# power.net
KiCad netlist of a schematic drawn in Altium Designer
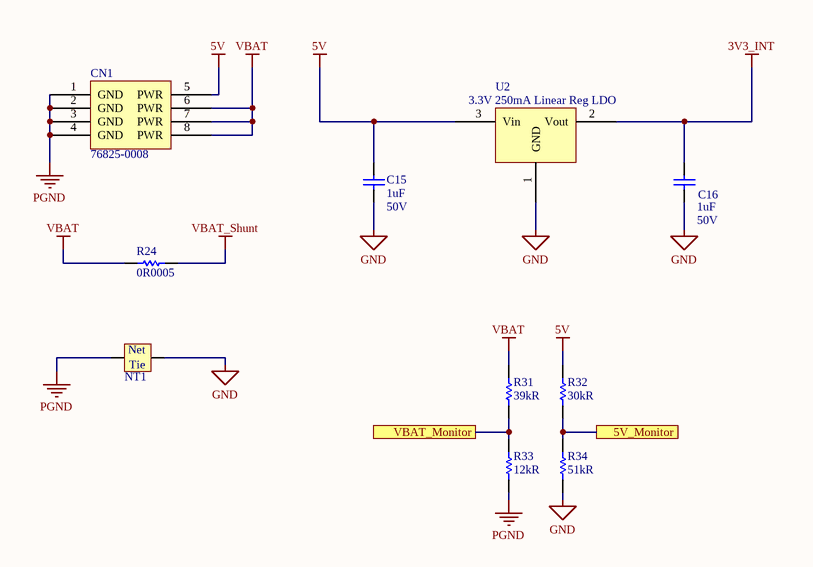
[diagram p0: power.SchDoc]

(export (version "E")
  (design (tool "Eeschema 10.0.6"))
  (components
    (comp (ref "C15")
      (value "CL21B105KBFNNNG")
      (footprint "0803 CAP")
      (description "SAMSUNG ELECTRO-MECHANICS - CL21B105KBFNNNG - MLCC CAPACITORS")
      (fields
        (field (name "CAPACITANCE") "1uF")
        (field (name "TOLERANCE") "10%")
        (field (name "VOLTAGE") "50V")
      )
      (libsource (lib "AUVIC") (part "Symbol"))
    )
    (comp (ref "C16")
      (value "CL21B105KBFNNNG")
      (footprint "0803 CAP")
      (description "SAMSUNG ELECTRO-MECHANICS - CL21B105KBFNNNG - MLCC CAPACITORS")
      (fields
        (field (name "TOLERANCE") "10%")
        (field (name "CAPACITANCE") "1uF")
        (field (name "VOLTAGE") "50V")
      )
      (libsource (lib "AUVIC") (part "Symbol"))
    )
    (comp (ref "CN1")
      (value "76825-0008")
      (footprint "76825-0008-Footprint-1")
      (description "MOLEX         76825-0008.             CONNECTOR, HEADER, 8POS, 2ROW, 5.7MM")
      (libsource (lib "AUVIC") (part "76825-0008"))
    )
    (comp (ref "NT1")
      (value "Net Tie, 20x3mm")
      (footprint "NETTIE_20x3mm")
      (fields
        (field (name "SOURCE") "AUVic_Integrated_Library_Virtual_Components.SchLib")
        (field (name "CREATED BY") "Ashwin Sira")
        (field (name "PUBLISHER") "AUVic")
      )
      (libsource (lib "") (part "Symbol_1"))
    )
    (comp (ref "R24")
      (value "0R0005")
      (footprint "RESC6332N(2512\")")
      (description "0R0005, 1%, 3W, 2512 SMD")
      (fields
        (field (name "MFG") "Riedon")
        (field (name "CREATED BY") "Ashwin Sira")
        (field (name "PUBLISHER") "AUVic")
      )
      (libsource (lib "") (part "Symbol_2"))
    )
    (comp (ref "R31")
      (value "CRCW060339K0FKEA")
      (footprint "FP-CRCW0603-e3-IPC_C")
      (description "Resistor; Thick Film; 39 Kilohms; 0.1 W; 1%; SMT; 0603; TCR 37 ppm/DegC; Cut Tape")
      (fields (field (name "RESISTANCE") "39kR") (field (name "TOLERANCE") "1%"))
      (libsource (lib "AUVIC") (part "RES"))
    )
    (comp (ref "R32")
      (value "CRCW060330K0FKEA")
      (footprint "RESC1609X50X30NL10T20")
      (description "Resistor SMD 30 kOhm 0603 PU=5000 ST, CRCW060330K0FKEA, Vishay")
      (fields (field (name "RESISTANCE") "30kR") (field (name "TOLERANCE") "1%"))
      (libsource (lib "AUVIC") (part "RES"))
    )
    (comp (ref "R33")
      (value "12kR, 1%, 1/10W, 0603")
      (footprint "RESC0603(1608)_L")
      (description "TE Connectivity CRG0603 Series Thick Film Surface Mount Resistor 0603 Case 12k 1% 0.1W 100ppm/C")
      (fields (field (name "TOLERANCE") "1%") (field (name "RESISTANCE") "12kR"))
      (libsource (lib "AUVIC") (part "RES"))
    )
    (comp (ref "R34")
      (value "CRCW060351K0FKEA")
      (footprint "RESC0603(1608)_N")
      (fields (field (name "RESISTANCE") "51kR") (field (name "TOLERANCE") "1%"))
      (libsource (lib "AUVIC") (part "RES"))
    )
    (comp (ref "U2")
      (value "3.3V 250mA Linear Reg LDO")
      (footprint "SOT95P245X110-3N")
      (description "IC REG LINEAR 3.3V 250MA SOT23-3")
      (fields (field (name "CREATED BY") "Poorna Chander Kalidas"))
      (libsource (lib "AUVIC") (part "3.3V 250mA Linear Reg LDO"))
    )
  )
  (nets
    (net (code "1") (name "/5V_Monitor") (class "Default")
      (node (ref "R32") (pin "2") (pinfunction "2_2") (pintype "passive"))
      (node (ref "R34") (pin "2") (pinfunction "2_2") (pintype "passive"))
    )
    (net (code "2") (name "/VBAT_Monitor") (class "Default")
      (node (ref "R31") (pin "1") (pinfunction "1_1") (pintype "passive"))
      (node (ref "R33") (pin "2") (pinfunction "2_2") (pintype "passive"))
    )
    (net (code "3") (name "3V3_INT") (class "Default")
      (node (ref "C16") (pin "2") (pinfunction "2_2") (pintype "passive"))
      (node (ref "U2") (pin "2") (pinfunction "Vout_2") (pintype "power_in"))
    )
    (net (code "4") (name "5V") (class "Default")
      (node (ref "C15") (pin "2") (pinfunction "2_2") (pintype "passive"))
      (node (ref "CN1") (pin "5") (pinfunction "PWR_5") (pintype "passive"))
      (node (ref "R32") (pin "1") (pinfunction "1_1") (pintype "passive"))
      (node (ref "U2") (pin "3") (pinfunction "Vin_3") (pintype "power_in"))
    )
    (net (code "5") (name "GND") (class "Default")
      (node (ref "C15") (pin "1") (pinfunction "1_1") (pintype "passive"))
      (node (ref "C16") (pin "1") (pinfunction "1_1") (pintype "passive"))
      (node (ref "NT1") (pin "2") (pinfunction "2_2") (pintype "passive"))
      (node (ref "R34") (pin "1") (pinfunction "1_1") (pintype "passive"))
      (node (ref "U2") (pin "1") (pinfunction "GND_1") (pintype "power_in"))
    )
    (net (code "6") (name "PGND") (class "Default")
      (node (ref "CN1") (pin "1") (pinfunction "GND_1") (pintype "passive"))
      (node (ref "CN1") (pin "2") (pinfunction "GND_2") (pintype "passive"))
      (node (ref "CN1") (pin "3") (pinfunction "GND_3") (pintype "passive"))
      (node (ref "CN1") (pin "4") (pinfunction "GND_4") (pintype "passive"))
      (node (ref "NT1") (pin "1") (pinfunction "1_1") (pintype "passive"))
      (node (ref "R33") (pin "1") (pinfunction "1_1") (pintype "passive"))
    )
    (net (code "7") (name "VBAT") (class "Default")
      (node (ref "CN1") (pin "6") (pinfunction "PWR_6") (pintype "passive"))
      (node (ref "CN1") (pin "7") (pinfunction "PWR_7") (pintype "passive"))
      (node (ref "CN1") (pin "8") (pinfunction "PWR_8") (pintype "passive"))
      (node (ref "R24") (pin "1") (pinfunction "1_1") (pintype "passive"))
      (node (ref "R31") (pin "2") (pinfunction "2_2") (pintype "passive"))
    )
    (net (code "8") (name "VBAT_Shunt") (class "Default")
      (node (ref "R24") (pin "2") (pinfunction "2_2") (pintype "passive"))
    )
  )
)
